# 11_FPGA_CONFIG.net
KiCad netlist of a schematic drawn in Altium Designer
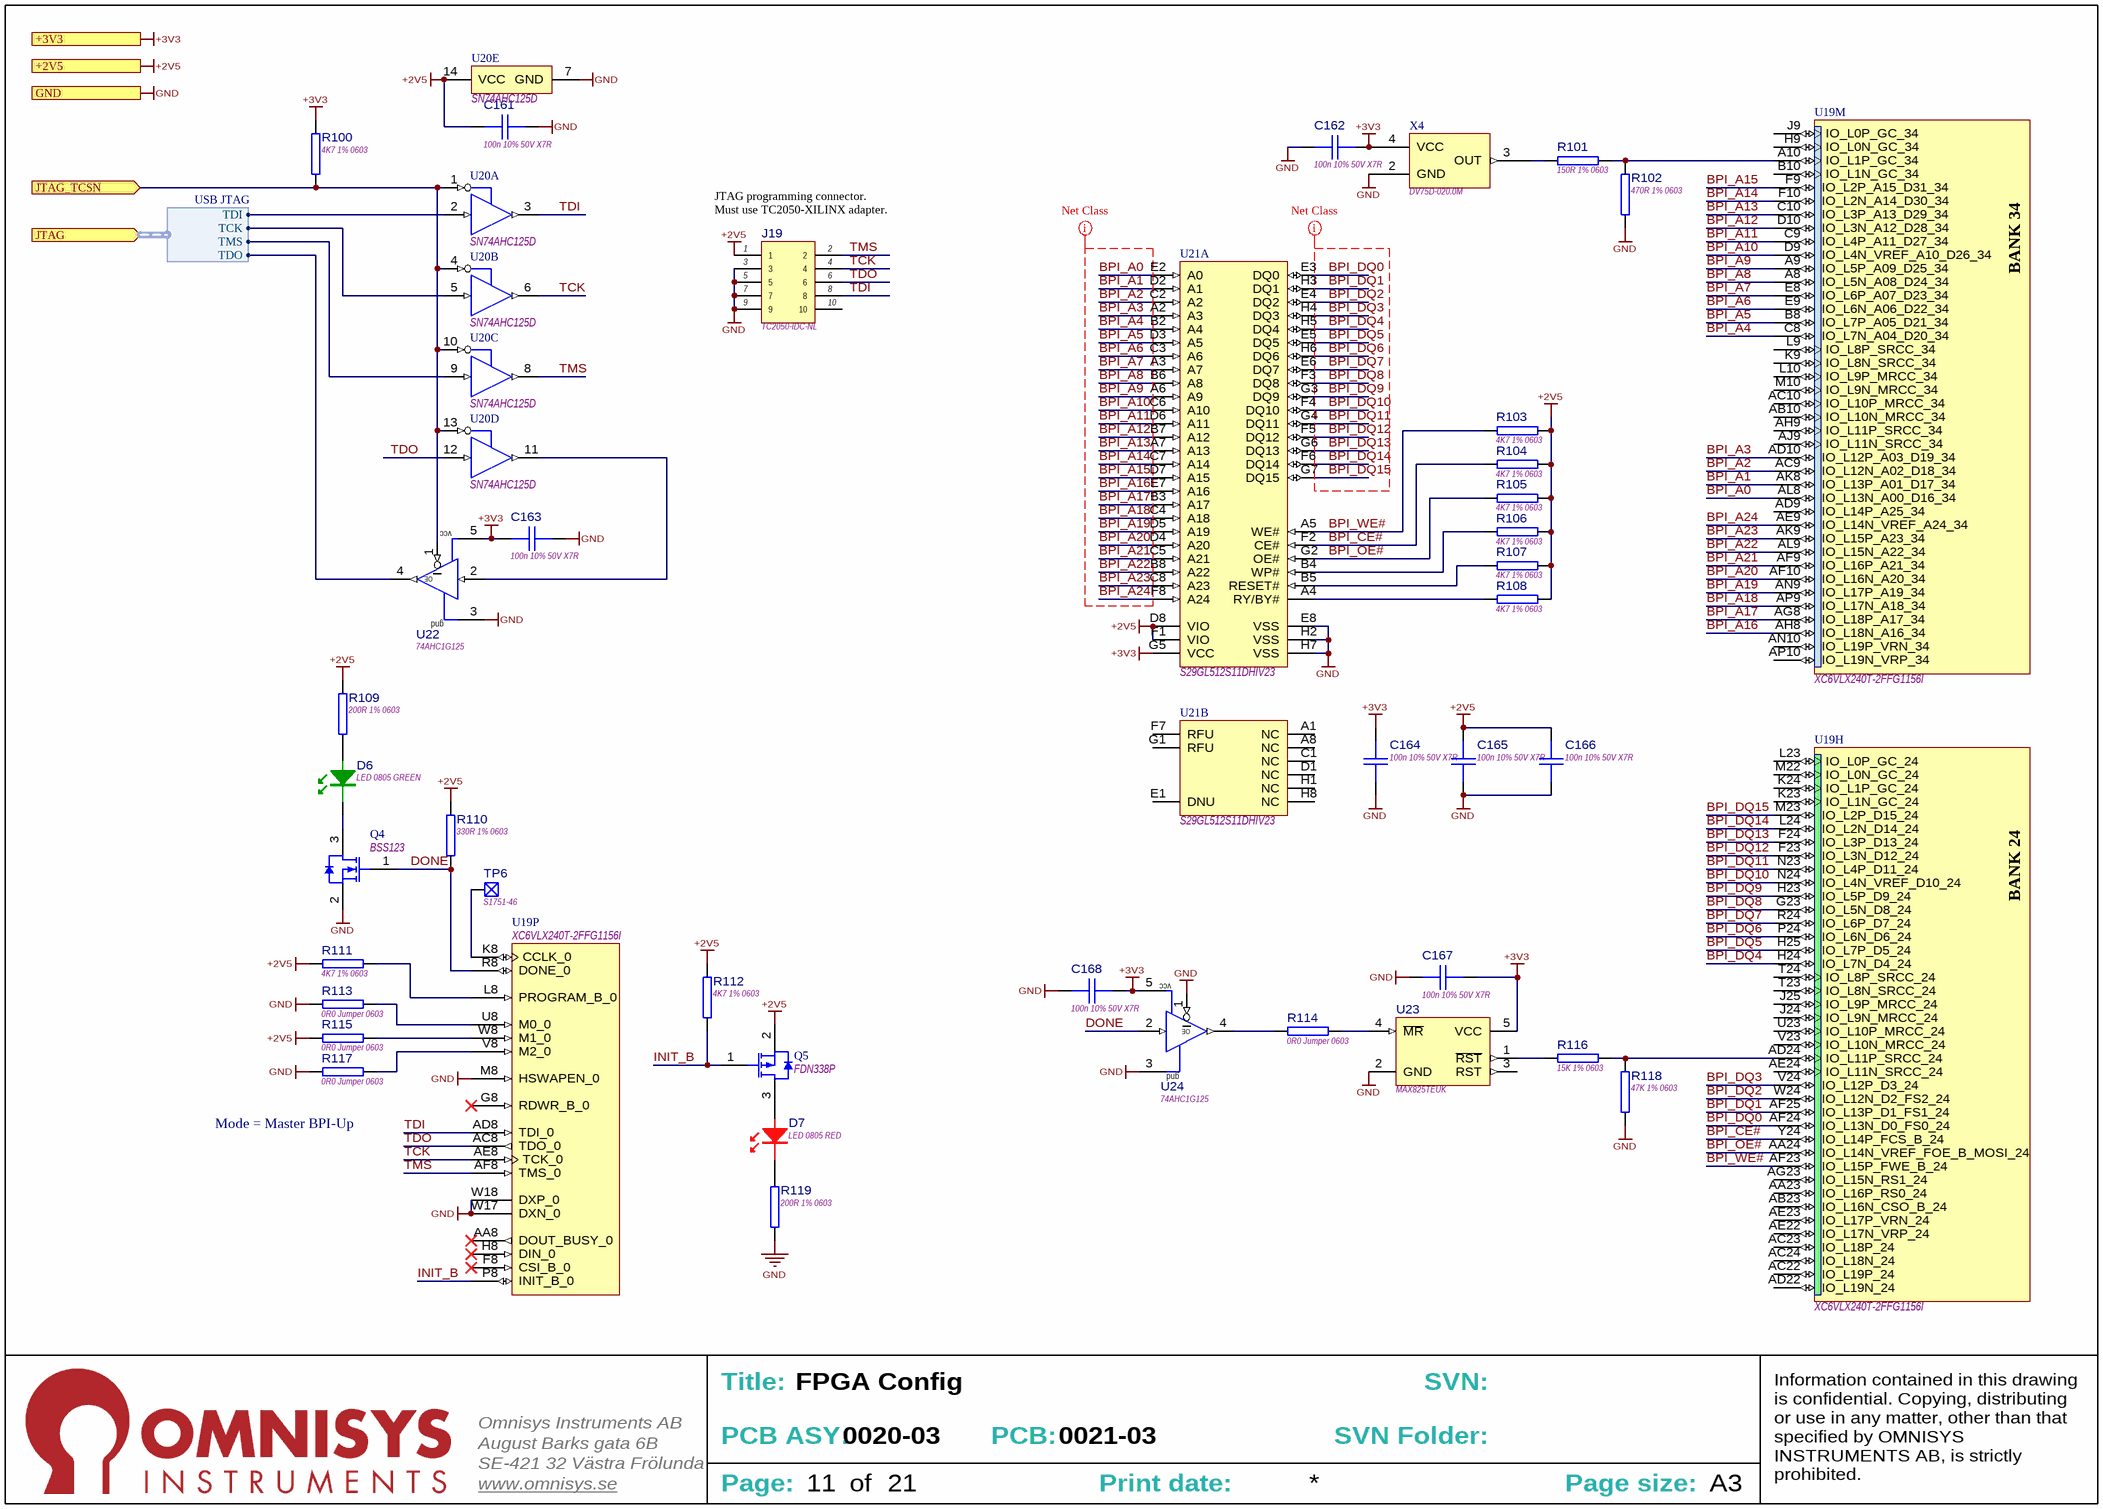
[diagram p0: [11] FPGA_CONFIG.SchDoc]

(export (version "E")
  (design (tool "Eeschema 10.0.6"))
  (components
    (comp (ref "C161")
      (value "100n 10% 50V X7R")
      (footprint "CAPC1608X90N")
      (description "Ceramic Chip Capacitor, 0603/1608")
      (fields (field (name "TOLERANCE") "10%"))
      (libsource (lib "Omnisys Vault") (part "CAP-2PIN"))
    )
    (comp (ref "C162")
      (value "100n 10% 50V X7R")
      (footprint "CAPC1608X90N")
      (description "Ceramic Chip Capacitor, 0603/1608")
      (fields (field (name "TOLERANCE") "10%"))
      (libsource (lib "Omnisys Vault") (part "CAP-2PIN"))
    )
    (comp (ref "C163")
      (value "100n 10% 50V X7R")
      (footprint "CAPC1608X90N")
      (description "Ceramic Chip Capacitor, 0603/1608")
      (fields (field (name "TOLERANCE") "10%"))
      (libsource (lib "Omnisys Vault") (part "CAP-2PIN"))
    )
    (comp (ref "C164")
      (value "100n 10% 50V X7R")
      (footprint "CAPC1608X90N")
      (description "Ceramic Chip Capacitor, 0603/1608")
      (fields (field (name "TOLERANCE") "10%"))
      (libsource (lib "Omnisys Vault") (part "CAP-2PIN"))
    )
    (comp (ref "C165")
      (value "100n 10% 50V X7R")
      (footprint "CAPC1608X90N")
      (description "Ceramic Chip Capacitor, 0603/1608")
      (fields (field (name "TOLERANCE") "10%"))
      (libsource (lib "Omnisys Vault") (part "CAP-2PIN"))
    )
    (comp (ref "C166")
      (value "100n 10% 50V X7R")
      (footprint "CAPC1608X90N")
      (description "Ceramic Chip Capacitor, 0603/1608")
      (fields (field (name "TOLERANCE") "10%"))
      (libsource (lib "Omnisys Vault") (part "CAP-2PIN"))
    )
    (comp (ref "C167")
      (value "100n 10% 50V X7R")
      (footprint "CAPC1608X90N")
      (description "Ceramic Chip Capacitor, 0603/1608")
      (fields (field (name "TOLERANCE") "10%"))
      (libsource (lib "Omnisys Vault") (part "CAP-2PIN"))
    )
    (comp (ref "C168")
      (value "100n 10% 50V X7R")
      (footprint "CAPC1608X90N")
      (description "Ceramic Chip Capacitor, 0603/1608")
      (fields (field (name "TOLERANCE") "10%"))
      (libsource (lib "Omnisys Vault") (part "CAP-2PIN"))
    )
    (comp (ref "D6")
      (value "LED 0805 GREEN")
      (footprint "LED2012-GREEN")
      (libsource (lib "Omnisys Vault") (part "LED-2PIN-GREEN"))
    )
    (comp (ref "D7")
      (value "LED 0805 RED")
      (footprint "LED2012-RED")
      (libsource (lib "Omnisys Vault") (part "LED-2PIN-RED"))
    )
    (comp (ref "J19")
      (value "TC2050-IDC-NL")
      (footprint "TC2050-IDC without connector")
      (description "CBL PLUG-OF-NAILS 10-PIN")
      (libsource (lib "Omnisys Vault") (part "CON-2ROW-10PIN"))
    )
    (comp (ref "Q4")
      (value "BSS123")
      (footprint "SOT95P230X110-3N")
      (description "MOSFET N-CH 100V 170MA SOT-23")
      (fields (field (name "VOLTAGE") "100V"))
      (libsource (lib "Omnisys Vault") (part "NEMOS-GSD-3"))
    )
    (comp (ref "Q5")
      (value "FDN338P")
      (footprint "SOT95P230X110-3N")
      (description "ON SEMICONDUCTOR - FDN338P - P CHANNEL MOSFET, -20V, 1.6A SUPER SOT-3")
      (libsource (lib "Omnisys Vault") (part "PEMOS-GSD-3"))
    )
    (comp (ref "R100")
      (value "4K7 1% 0603")
      (footprint "RESC1608N")
      (description "Thick film Chip Resistor, 0603/1608")
      (fields (field (name "POWER") "100mW") (field (name "TOLERANCE") "1%"))
      (libsource (lib "Omnisys Vault") (part "RES-2PIN"))
    )
    (comp (ref "R101")
      (value "150R 1% 0603")
      (footprint "RESC1608N")
      (description "Thick film Chip Resistor, 0603/1608")
      (fields (field (name "POWER") "100mW") (field (name "TOLERANCE") "1%"))
      (libsource (lib "Omnisys Vault") (part "RES-2PIN"))
    )
    (comp (ref "R102")
      (value "470R 1% 0603")
      (footprint "RESC1608N")
      (description "Thick film Chip Resistor, 0603/1608")
      (fields (field (name "POWER") "100mW") (field (name "TOLERANCE") "1%"))
      (libsource (lib "Omnisys Vault") (part "RES-2PIN"))
    )
    (comp (ref "R103")
      (value "4K7 1% 0603")
      (footprint "RESC1608N")
      (description "Thick film Chip Resistor, 0603/1608")
      (fields (field (name "POWER") "100mW") (field (name "TOLERANCE") "1%"))
      (libsource (lib "Omnisys Vault") (part "RES-2PIN"))
    )
    (comp (ref "R104")
      (value "4K7 1% 0603")
      (footprint "RESC1608N")
      (description "Thick film Chip Resistor, 0603/1608")
      (fields (field (name "POWER") "100mW") (field (name "TOLERANCE") "1%"))
      (libsource (lib "Omnisys Vault") (part "RES-2PIN"))
    )
    (comp (ref "R105")
      (value "4K7 1% 0603")
      (footprint "RESC1608N")
      (description "Thick film Chip Resistor, 0603/1608")
      (fields (field (name "POWER") "100mW") (field (name "TOLERANCE") "1%"))
      (libsource (lib "Omnisys Vault") (part "RES-2PIN"))
    )
    (comp (ref "R106")
      (value "4K7 1% 0603")
      (footprint "RESC1608N")
      (description "Thick film Chip Resistor, 0603/1608")
      (fields (field (name "POWER") "100mW") (field (name "TOLERANCE") "1%"))
      (libsource (lib "Omnisys Vault") (part "RES-2PIN"))
    )
    (comp (ref "R107")
      (value "4K7 1% 0603")
      (footprint "RESC1608N")
      (description "Thick film Chip Resistor, 0603/1608")
      (fields (field (name "POWER") "100mW") (field (name "TOLERANCE") "1%"))
      (libsource (lib "Omnisys Vault") (part "RES-2PIN"))
    )
    (comp (ref "R108")
      (value "4K7 1% 0603")
      (footprint "RESC1608N")
      (description "Thick film Chip Resistor, 0603/1608")
      (fields (field (name "POWER") "100mW") (field (name "TOLERANCE") "1%"))
      (libsource (lib "Omnisys Vault") (part "RES-2PIN"))
    )
    (comp (ref "R109")
      (value "200R 1% 0603")
      (footprint "RESC1608N")
      (description "Thick film Chip Resistor, 0603/1608")
      (fields (field (name "POWER") "100mW") (field (name "TOLERANCE") "1%"))
      (libsource (lib "Omnisys Vault") (part "RES-2PIN"))
    )
    (comp (ref "R110")
      (value "330R 1% 0603")
      (footprint "RESC1608N")
      (description "Thick film Chip Resistor, 0603/1608")
      (fields (field (name "POWER") "100mW") (field (name "TOLERANCE") "1%"))
      (libsource (lib "Omnisys Vault") (part "RES-2PIN"))
    )
    (comp (ref "R111")
      (value "4K7 1% 0603")
      (footprint "RESC1608N")
      (description "Thick film Chip Resistor, 0603/1608")
      (fields (field (name "POWER") "100mW") (field (name "TOLERANCE") "1%"))
      (libsource (lib "Omnisys Vault") (part "RES-2PIN"))
    )
    (comp (ref "R112")
      (value "4K7 1% 0603")
      (footprint "RESC1608N")
      (description "Thick film Chip Resistor, 0603/1608")
      (fields (field (name "POWER") "100mW") (field (name "TOLERANCE") "1%"))
      (libsource (lib "Omnisys Vault") (part "RES-2PIN"))
    )
    (comp (ref "R113")
      (value "0R0 Jumper 0603")
      (footprint "RESC1608N")
      (description "Thick film Chip Resistor, 0603/1608")
      (fields (field (name "TOLERANCE") "0%") (field (name "POWER") "0W"))
      (libsource (lib "Omnisys Vault") (part "RES-2PIN"))
    )
    (comp (ref "R114")
      (value "0R0 Jumper 0603")
      (footprint "RESC1608N")
      (description "Thick film Chip Resistor, 0603/1608")
      (fields (field (name "TOLERANCE") "0%") (field (name "POWER") "0W"))
      (libsource (lib "Omnisys Vault") (part "RES-2PIN"))
    )
    (comp (ref "R115")
      (value "0R0 Jumper 0603")
      (footprint "RESC1608N")
      (description "Thick film Chip Resistor, 0603/1608")
      (fields (field (name "TOLERANCE") "0%") (field (name "POWER") "0W"))
      (libsource (lib "Omnisys Vault") (part "RES-2PIN"))
    )
    (comp (ref "R116")
      (value "15K 1% 0603")
      (footprint "RESC1608N")
      (description "Thick film Chip Resistor, 0603/1608")
      (fields (field (name "POWER") "100mW") (field (name "TOLERANCE") "1%"))
      (libsource (lib "Omnisys Vault") (part "RES-2PIN"))
    )
    (comp (ref "R117")
      (value "0R0 Jumper 0603")
      (footprint "RESC1608N")
      (description "Thick film Chip Resistor, 0603/1608")
      (fields (field (name "TOLERANCE") "0%") (field (name "POWER") "0W"))
      (libsource (lib "Omnisys Vault") (part "RES-2PIN"))
    )
    (comp (ref "R118")
      (value "47K 1% 0603")
      (footprint "RESC1608N")
      (description "Thick film Chip Resistor, 0603/1608")
      (fields (field (name "POWER") "100mW") (field (name "TOLERANCE") "1%"))
      (libsource (lib "Omnisys Vault") (part "RES-2PIN"))
    )
    (comp (ref "R119")
      (value "200R 1% 0603")
      (footprint "RESC1608N")
      (description "Thick film Chip Resistor, 0603/1608")
      (fields (field (name "POWER") "100mW") (field (name "TOLERANCE") "1%"))
      (libsource (lib "Omnisys Vault") (part "RES-2PIN"))
    )
    (comp (ref "TP6")
      (value "S1751-46")
      (footprint "S1751-46")
      (description "SMD Test point clip")
      (libsource (lib "Omnisys Vault") (part "1-PIN_TP"))
    )
    (comp (ref "U19")
      (value "XC6VLX240T-2FFG1156I")
      (footprint "FFG1156")
      (description "FPGA Virtex-6 LXT Family 241152 Cells 40nm (CMOS) Technology 1V 1156-Pin FCBGA")
      (libsource (lib "Omnisys Vault") (part "FPGA-XVR6-XC6VXXXXXT-GA1156"))
    )
    (comp (ref "U20")
      (value "SN74AHC125D")
      (footprint "SOIC127P600X175-14N")
      (description "Buffer/Line Driver 4-CH Non-Inverting 3-ST CMOS 14-Pin SOIC Tube")
      (libsource (lib "Omnisys Vault") (part "SN74AHC125D"))
    )
    (comp (ref "U21")
      (value "S29GL512S11DHIV23")
      (footprint "BGA64C100P8X8_900X900X140")
      (description "IC FLASH MEM 512MBIT PAGE 64BGA")
      (libsource (lib "Omnisys Vault") (part "S29GL512S11DHIV23"))
    )
    (comp (ref "U22")
      (value "74AHC1G125")
      (footprint "SOT95P280X100-5N")
      (description "Single bus buffer gate with 3-state output")
      (libsource (lib "Omnisys Vault") (part "74AHC1G125"))
    )
    (comp (ref "U23")
      (value "MAX825TEUK")
      (footprint "SOT95P280X100-5N")
      (description "Microprocessor Supervisory Circuits With Watchdog Timer and Manual Reset SOT-23-5, reset th: 3.08V")
      (libsource (lib "Omnisys Vault") (part "MAX825_EUK"))
    )
    (comp (ref "U24")
      (value "74AHC1G125")
      (footprint "SOT95P280X100-5N")
      (description "Single bus buffer gate with 3-state output")
      (libsource (lib "Omnisys Vault") (part "74AHC1G125"))
    )
    (comp (ref "X4")
      (value "DV75D-020.0M")
      (footprint "DV75D")
      (description "OSC TCXO 20.000MHZ LVCMOS SMD")
      (libsource (lib "Omnisys Vault") (part "DV75D-020.0M"))
    )
  )
  (nets
    (net (code "3") (name "+2V5") (class "Default")
      (node (ref "C161") (pin "1") (pinfunction "1_1") (pintype "passive"))
      (node (ref "C165") (pin "1") (pinfunction "1_1") (pintype "passive"))
      (node (ref "C166") (pin "1") (pinfunction "1_1") (pintype "passive"))
      (node (ref "J19") (pin "1") (pinfunction "1_1") (pintype "passive"))
      (node (ref "Q5") (pin "2") (pinfunction "SOURCE_2") (pintype "passive"))
      (node (ref "R103") (pin "1") (pinfunction "1_1") (pintype "passive"))
      (node (ref "R104") (pin "1") (pinfunction "1_1") (pintype "passive"))
      (node (ref "R105") (pin "1") (pinfunction "1_1") (pintype "passive"))
      (node (ref "R106") (pin "1") (pinfunction "1_1") (pintype "passive"))
      (node (ref "R107") (pin "1") (pinfunction "1_1") (pintype "passive"))
      (node (ref "R108") (pin "1") (pinfunction "1_1") (pintype "passive"))
      (node (ref "R109") (pin "2") (pinfunction "2_2") (pintype "passive"))
      (node (ref "R110") (pin "1") (pinfunction "1_1") (pintype "passive"))
      (node (ref "R111") (pin "2") (pinfunction "2_2") (pintype "passive"))
      (node (ref "R112") (pin "1") (pinfunction "1_1") (pintype "passive"))
      (node (ref "R115") (pin "1") (pinfunction "1_1") (pintype "passive"))
      (node (ref "U20") (pin "14") (pinfunction "VCC_14") (pintype "power_in"))
      (node (ref "U21") (pin "D8") (pinfunction "VIO_D8") (pintype "power_in"))
      (node (ref "U21") (pin "F1") (pinfunction "VIO_F1") (pintype "power_in"))
    )
    (net (code "4") (name "+3V3") (class "Default")
      (node (ref "C162") (pin "1") (pinfunction "1_1") (pintype "passive"))
      (node (ref "C163") (pin "1") (pinfunction "1_1") (pintype "passive"))
      (node (ref "C164") (pin "1") (pinfunction "1_1") (pintype "passive"))
      (node (ref "C167") (pin "2") (pinfunction "2_2") (pintype "passive"))
      (node (ref "C168") (pin "1") (pinfunction "1_1") (pintype "passive"))
      (node (ref "R100") (pin "2") (pinfunction "2_2") (pintype "passive"))
      (node (ref "U21") (pin "G5") (pinfunction "VCC_G5") (pintype "power_in"))
      (node (ref "U22") (pin "5") (pinfunction "VCC_5") (pintype "power_in"))
      (node (ref "U23") (pin "5") (pinfunction "VCC_5") (pintype "power_in"))
      (node (ref "U24") (pin "5") (pinfunction "VCC_5") (pintype "power_in"))
      (node (ref "X4") (pin "4") (pinfunction "VCC_4") (pintype "power_in"))
    )
    (net (code "5") (name "/BPI_A0") (class "Default")
      (node (ref "U19") (pin "AL8") (pinfunction "IO_L13N_A00_D16_34_AL8") (pintype "bidirectional"))
      (node (ref "U21") (pin "E2") (pinfunction "A0_E2") (pintype "input"))
    )
    (net (code "6") (name "/BPI_A1") (class "Default")
      (node (ref "U19") (pin "AK8") (pinfunction "IO_L13P_A01_D17_34_AK8") (pintype "bidirectional"))
      (node (ref "U21") (pin "D2") (pinfunction "A1_D2") (pintype "input"))
    )
    (net (code "7") (name "/BPI_A2") (class "Default")
      (node (ref "U19") (pin "AC9") (pinfunction "IO_L12N_A02_D18_34_AC9") (pintype "bidirectional"))
      (node (ref "U21") (pin "C2") (pinfunction "A2_C2") (pintype "input"))
    )
    (net (code "8") (name "/BPI_A3") (class "Default")
      (node (ref "U19") (pin "AD10") (pinfunction "IO_L12P_A03_D19_34_AD10") (pintype "bidirectional"))
      (node (ref "U21") (pin "A2") (pinfunction "A3_A2") (pintype "input"))
    )
    (net (code "9") (name "/BPI_A4") (class "Default")
      (node (ref "U19") (pin "C8") (pinfunction "IO_L7N_A04_D20_34_C8") (pintype "bidirectional"))
      (node (ref "U21") (pin "B2") (pinfunction "A4_B2") (pintype "input"))
    )
    (net (code "10") (name "/BPI_A5") (class "Default")
      (node (ref "U19") (pin "B8") (pinfunction "IO_L7P_A05_D21_34_B8") (pintype "bidirectional"))
      (node (ref "U21") (pin "D3") (pinfunction "A5_D3") (pintype "input"))
    )
    (net (code "11") (name "/BPI_A6") (class "Default")
      (node (ref "U19") (pin "E9") (pinfunction "IO_L6N_A06_D22_34_E9") (pintype "bidirectional"))
      (node (ref "U21") (pin "C3") (pinfunction "A6_C3") (pintype "input"))
    )
    (net (code "12") (name "/BPI_A7") (class "Default")
      (node (ref "U19") (pin "E8") (pinfunction "IO_L6P_A07_D23_34_E8") (pintype "bidirectional"))
      (node (ref "U21") (pin "A3") (pinfunction "A7_A3") (pintype "input"))
    )
    (net (code "13") (name "/BPI_A8") (class "Default")
      (node (ref "U19") (pin "A8") (pinfunction "IO_L5N_A08_D24_34_A8") (pintype "bidirectional"))
      (node (ref "U21") (pin "B6") (pinfunction "A8_B6") (pintype "input"))
    )
    (net (code "14") (name "/BPI_A9") (class "Default")
      (node (ref "U19") (pin "A9") (pinfunction "IO_L5P_A09_D25_34_A9") (pintype "bidirectional"))
      (node (ref "U21") (pin "A6") (pinfunction "A9_A6") (pintype "input"))
    )
    (net (code "15") (name "/BPI_A10") (class "Default")
      (node (ref "U19") (pin "D9") (pinfunction "IO_L4N_VREF_A10_D26_34_D9") (pintype "bidirectional"))
      (node (ref "U21") (pin "C6") (pinfunction "A10_C6") (pintype "input"))
    )
    (net (code "16") (name "/BPI_A11") (class "Default")
      (node (ref "U19") (pin "C9") (pinfunction "IO_L4P_A11_D27_34_C9") (pintype "bidirectional"))
      (node (ref "U21") (pin "D6") (pinfunction "A11_D6") (pintype "input"))
    )
    (net (code "17") (name "/BPI_A12") (class "Default")
      (node (ref "U19") (pin "D10") (pinfunction "IO_L3N_A12_D28_34_D10") (pintype "bidirectional"))
      (node (ref "U21") (pin "B7") (pinfunction "A12_B7") (pintype "input"))
    )
    (net (code "18") (name "/BPI_A13") (class "Default")
      (node (ref "U19") (pin "C10") (pinfunction "IO_L3P_A13_D29_34_C10") (pintype "bidirectional"))
      (node (ref "U21") (pin "A7") (pinfunction "A13_A7") (pintype "input"))
    )
    (net (code "19") (name "/BPI_A14") (class "Default")
      (node (ref "U19") (pin "F10") (pinfunction "IO_L2N_A14_D30_34_F10") (pintype "bidirectional"))
      (node (ref "U21") (pin "C7") (pinfunction "A14_C7") (pintype "input"))
    )
    (net (code "20") (name "/BPI_A15") (class "Default")
      (node (ref "U19") (pin "F9") (pinfunction "IO_L2P_A15_D31_34_F9") (pintype "bidirectional"))
      (node (ref "U21") (pin "D7") (pinfunction "A15_D7") (pintype "input"))
    )
    (net (code "21") (name "/BPI_A16") (class "Default")
      (node (ref "U19") (pin "AH8") (pinfunction "IO_L18N_A16_34_AH8") (pintype "bidirectional"))
      (node (ref "U21") (pin "E7") (pinfunction "A16_E7") (pintype "input"))
    )
    (net (code "22") (name "/BPI_A17") (class "Default")
      (node (ref "U19") (pin "AG8") (pinfunction "IO_L18P_A17_34_AG8") (pintype "bidirectional"))
      (node (ref "U21") (pin "B3") (pinfunction "A17_B3") (pintype "input"))
    )
    (net (code "23") (name "/BPI_A18") (class "Default")
      (node (ref "U19") (pin "AP9") (pinfunction "IO_L17N_A18_34_AP9") (pintype "bidirectional"))
      (node (ref "U21") (pin "C4") (pinfunction "A18_C4") (pintype "input"))
    )
    (net (code "24") (name "/BPI_A19") (class "Default")
      (node (ref "U19") (pin "AN9") (pinfunction "IO_L17P_A19_34_AN9") (pintype "bidirectional"))
      (node (ref "U21") (pin "D5") (pinfunction "A19_D5") (pintype "input"))
    )
    (net (code "25") (name "/BPI_A20") (class "Default")
      (node (ref "U19") (pin "AF10") (pinfunction "IO_L16N_A20_34_AF10") (pintype "bidirectional"))
      (node (ref "U21") (pin "D4") (pinfunction "A20_D4") (pintype "input"))
    )
    (net (code "26") (name "/BPI_A21") (class "Default")
      (node (ref "U19") (pin "AF9") (pinfunction "IO_L16P_A21_34_AF9") (pintype "bidirectional"))
      (node (ref "U21") (pin "C5") (pinfunction "A21_C5") (pintype "input"))
    )
    (net (code "27") (name "/BPI_A22") (class "Default")
      (node (ref "U19") (pin "AL9") (pinfunction "IO_L15N_A22_34_AL9") (pintype "bidirectional"))
      (node (ref "U21") (pin "B8") (pinfunction "A22_B8") (pintype "input"))
    )
    (net (code "28") (name "/BPI_A23") (class "Default")
      (node (ref "U19") (pin "AK9") (pinfunction "IO_L15P_A23_34_AK9") (pintype "bidirectional"))
      (node (ref "U21") (pin "C8") (pinfunction "A23_C8") (pintype "input"))
    )
    (net (code "29") (name "/BPI_A24") (class "Default")
      (node (ref "U19") (pin "AE9") (pinfunction "IO_L14N_VREF_A24_34_AE9") (pintype "bidirectional"))
      (node (ref "U21") (pin "F8") (pinfunction "A24_F8") (pintype "input"))
    )
    (net (code "30") (name "/BPI_CE#") (class "Default")
      (node (ref "R104") (pin "2") (pinfunction "2_2") (pintype "passive"))
      (node (ref "U19") (pin "Y24") (pinfunction "IO_L14P_FCS_B_24_Y24") (pintype "bidirectional"))
      (node (ref "U21") (pin "F2") (pinfunction "CE#_F2") (pintype "input"))
    )
    (net (code "31") (name "/BPI_DQ0") (class "Default")
      (node (ref "U19") (pin "AF24") (pinfunction "IO_L13N_D0_FS0_24_AF24") (pintype "bidirectional"))
      (node (ref "U21") (pin "E3") (pinfunction "DQ0_E3") (pintype "bidirectional"))
    )
    (net (code "32") (name "/BPI_DQ1") (class "Default")
      (node (ref "U19") (pin "AF25") (pinfunction "IO_L13P_D1_FS1_24_AF25") (pintype "bidirectional"))
      (node (ref "U21") (pin "H3") (pinfunction "DQ1_H3") (pintype "bidirectional"))
    )
    (net (code "33") (name "/BPI_DQ2") (class "Default")
      (node (ref "U19") (pin "W24") (pinfunction "IO_L12N_D2_FS2_24_W24") (pintype "bidirectional"))
      (node (ref "U21") (pin "E4") (pinfunction "DQ2_E4") (pintype "bidirectional"))
    )
    (net (code "34") (name "/BPI_DQ3") (class "Default")
      (node (ref "U19") (pin "V24") (pinfunction "IO_L12P_D3_24_V24") (pintype "bidirectional"))
      (node (ref "U21") (pin "H4") (pinfunction "DQ3_H4") (pintype "bidirectional"))
    )
    (net (code "35") (name "/BPI_DQ4") (class "Default")
      (node (ref "U19") (pin "H24") (pinfunction "IO_L7N_D4_24_H24") (pintype "bidirectional"))
      (node (ref "U21") (pin "H5") (pinfunction "DQ4_H5") (pintype "bidirectional"))
    )
    (net (code "36") (name "/BPI_DQ5") (class "Default")
      (node (ref "U19") (pin "H25") (pinfunction "IO_L7P_D5_24_H25") (pintype "bidirectional"))
      (node (ref "U21") (pin "E5") (pinfunction "DQ5_E5") (pintype "bidirectional"))
    )
    (net (code "37") (name "/BPI_DQ6") (class "Default")
      (node (ref "U19") (pin "P24") (pinfunction "IO_L6N_D6_24_P24") (pintype "bidirectional"))
      (node (ref "U21") (pin "H6") (pinfunction "DQ6_H6") (pintype "bidirectional"))
    )
    (net (code "38") (name "/BPI_DQ7") (class "Default")
      (node (ref "U19") (pin "R24") (pinfunction "IO_L6P_D7_24_R24") (pintype "bidirectional"))
      (node (ref "U21") (pin "E6") (pinfunction "DQ7_E6") (pintype "bidirectional"))
    )
    (net (code "39") (name "/BPI_DQ8") (class "Default")
      (node (ref "U19") (pin "G23") (pinfunction "IO_L5N_D8_24_G23") (pintype "bidirectional"))
      (node (ref "U21") (pin "F3") (pinfunction "DQ8_F3") (pintype "bidirectional"))
    )
    (net (code "40") (name "/BPI_DQ9") (class "Default")
      (node (ref "U19") (pin "H23") (pinfunction "IO_L5P_D9_24_H23") (pintype "bidirectional"))
      (node (ref "U21") (pin "G3") (pinfunction "DQ9_G3") (pintype "bidirectional"))
    )
    (net (code "41") (name "/BPI_DQ10") (class "Default")
      (node (ref "U19") (pin "N24") (pinfunction "IO_L4N_VREF_D10_24_N24") (pintype "bidirectional"))
      (node (ref "U21") (pin "F4") (pinfunction "DQ10_F4") (pintype "bidirectional"))
    )
    (net (code "42") (name "/BPI_DQ11") (class "Default")
      (node (ref "U19") (pin "N23") (pinfunction "IO_L4P_D11_24_N23") (pintype "bidirectional"))
      (node (ref "U21") (pin "G4") (pinfunction "DQ11_G4") (pintype "bidirectional"))
    )
    (net (code "43") (name "/BPI_DQ12") (class "Default")
      (node (ref "U19") (pin "F23") (pinfunction "IO_L3N_D12_24_F23") (pintype "bidirectional"))
      (node (ref "U21") (pin "F5") (pinfunction "DQ12_F5") (pintype "bidirectional"))
    )
    (net (code "44") (name "/BPI_DQ13") (class "Default")
      (node (ref "U19") (pin "F24") (pinfunction "IO_L3P_D13_24_F24") (pintype "bidirectional"))
      (node (ref "U21") (pin "G6") (pinfunction "DQ13_G6") (pintype "bidirectional"))
    )
    (net (code "45") (name "/BPI_DQ14") (class "Default")
      (node (ref "U19") (pin "L24") (pinfunction "IO_L2N_D14_24_L24") (pintype "bidirectional"))
      (node (ref "U21") (pin "F6") (pinfunction "DQ14_F6") (pintype "bidirectional"))
    )
    (net (code "46") (name "/BPI_DQ15") (class "Default")
      (node (ref "U19") (pin "M23") (pinfunction "IO_L2P_D15_24_M23") (pintype "bidirectional"))
      (node (ref "U21") (pin "G7") (pinfunction "DQ15_G7") (pintype "bidirectional"))
    )
    (net (code "47") (name "/BPI_OE#") (class "Default")
      (node (ref "R105") (pin "2") (pinfunction "2_2") (pintype "passive"))
      (node (ref "U19") (pin "AA24") (pinfunction "IO_L14N_VREF_FOE_B_MOSI_24_AA24") (pintype "bidirectional"))
      (node (ref "U21") (pin "G2") (pinfunction "OE#_G2") (pintype "input"))
    )
    (net (code "48") (name "/BPI_WE#") (class "Default")
      (node (ref "R103") (pin "2") (pinfunction "2_2") (pintype "passive"))
      (node (ref "U19") (pin "AF23") (pinfunction "IO_L15P_FWE_B_24_AF23") (pintype "bidirectional"))
      (node (ref "U21") (pin "A5") (pinfunction "WE#_A5") (pintype "input"))
    )
    (net (code "49") (name "/DONE") (class "Default")
      (node (ref "Q4") (pin "1") (pinfunction "G_1") (pintype "passive"))
      (node (ref "R110") (pin "2") (pinfunction "2_2") (pintype "passive"))
      (node (ref "U19") (pin "R8") (pinfunction "DONE_0_R8") (pintype "bidirectional"))
      (node (ref "U24") (pin "2") (pinfunction "B_2") (pintype "input"))
    )
    (net (code "50") (name "/INIT_B") (class "Default")
      (node (ref "Q5") (pin "1") (pinfunction "GATE_1") (pintype "passive"))
      (node (ref "R112") (pin "2") (pinfunction "2_2") (pintype "passive"))
      (node (ref "U19") (pin "P8") (pinfunction "INIT_B_0_P8") (pintype "bidirectional"))
    )
    (net (code "51") (name "/JTAG_TCSN") (class "Default")
      (node (ref "R100") (pin "1") (pinfunction "1_1") (pintype "passive"))
      (node (ref "U20") (pin "1") (pinfunction "1OE#_1") (pintype "input"))
      (node (ref "U20") (pin "10") (pinfunction "3OE#_10") (pintype "input"))
      (node (ref "U20") (pin "13") (pinfunction "4OE#_13") (pintype "input"))
      (node (ref "U20") (pin "4") (pinfunction "2OE#_4") (pintype "input"))
      (node (ref "U22") (pin "1") (pinfunction "~{O}E_1") (pintype "input"))
    )
    (net (code "52") (name "/TCK") (class "Default")
      (node (ref "J19") (pin "4") (pinfunction "4_4") (pintype "passive"))
      (node (ref "U19") (pin "AE8") (pinfunction "TCK_0_AE8") (pintype "input"))
      (node (ref "U20") (pin "6") (pinfunction "2Y_6") (pintype "output"))
    )
    (net (code "53") (name "/TDI") (class "Default")
      (node (ref "J19") (pin "8") (pinfunction "8_8") (pintype "passive"))
      (node (ref "U19") (pin "AD8") (pinfunction "TDI_0_AD8") (pintype "input"))
      (node (ref "U20") (pin "3") (pinfunction "1Y_3") (pintype "output"))
    )
    (net (code "54") (name "/TDO") (class "Default")
      (node (ref "J19") (pin "6") (pinfunction "6_6") (pintype "passive"))
      (node (ref "U19") (pin "AC8") (pinfunction "TDO_0_AC8") (pintype "output"))
      (node (ref "U20") (pin "12") (pinfunction "4A_12") (pintype "input"))
    )
    (net (code "55") (name "/TMS") (class "Default")
      (node (ref "J19") (pin "2") (pinfunction "2_2") (pintype "passive"))
      (node (ref "U19") (pin "AF8") (pinfunction "TMS_0_AF8") (pintype "input"))
      (node (ref "U20") (pin "8") (pinfunction "3Y_8") (pintype "output"))
    )
    (net (code "57") (name "GND") (class "Default")
      (node (ref "C161") (pin "2") (pinfunction "2_2") (pintype "passive"))
      (node (ref "C162") (pin "2") (pinfunction "2_2") (pintype "passive"))
      (node (ref "C163") (pin "2") (pinfunction "2_2") (pintype "passive"))
      (node (ref "C164") (pin "2") (pinfunction "2_2") (pintype "passive"))
      (node (ref "C165") (pin "2") (pinfunction "2_2") (pintype "passive"))
      (node (ref "C166") (pin "2") (pinfunction "2_2") (pintype "passive"))
      (node (ref "C167") (pin "1") (pinfunction "1_1") (pintype "passive"))
      (node (ref "C168") (pin "2") (pinfunction "2_2") (pintype "passive"))
      (node (ref "J19") (pin "3") (pinfunction "3_3") (pintype "passive"))
      (node (ref "J19") (pin "5") (pinfunction "5_5") (pintype "passive"))
      (node (ref "J19") (pin "7") (pinfunction "7_7") (pintype "passive"))
      (node (ref "J19") (pin "9") (pinfunction "9_9") (pintype "passive"))
      (node (ref "Q4") (pin "2") (pinfunction "S_2") (pintype "passive"))
      (node (ref "R102") (pin "1") (pinfunction "1_1") (pintype "passive"))
      (node (ref "R113") (pin "1") (pinfunction "1_1") (pintype "passive"))
      (node (ref "R117") (pin "1") (pinfunction "1_1") (pintype "passive"))
      (node (ref "R118") (pin "1") (pinfunction "1_1") (pintype "passive"))
      (node (ref "R119") (pin "1") (pinfunction "1_1") (pintype "passive"))
      (node (ref "U19") (pin "M8") (pinfunction "HSWAPEN_0_M8") (pintype "input"))
      (node (ref "U19") (pin "W17") (pinfunction "DXN_0_W17") (pintype "passive"))
      (node (ref "U19") (pin "W18") (pinfunction "DXP_0_W18") (pintype "passive"))
      (node (ref "U20") (pin "7") (pinfunction "GND_7") (pintype "power_in"))
      (node (ref "U21") (pin "E8") (pinfunction "VSS_E8") (pintype "power_in"))
      (node (ref "U21") (pin "H2") (pinfunction "VSS_H2") (pintype "power_in"))
      (node (ref "U21") (pin "H7") (pinfunction "VSS_H7") (pintype "power_in"))
      (node (ref "U22") (pin "3") (pinfunction "GND_3") (pintype "power_in"))
      (node (ref "U23") (pin "2") (pinfunction "GND_2") (pintype "power_in"))
      (node (ref "U24") (pin "1") (pinfunction "~{O}E_1") (pintype "input"))
      (node (ref "U24") (pin "3") (pinfunction "GND_3") (pintype "power_in"))
      (node (ref "X4") (pin "2") (pinfunction "GND_2") (pintype "power_in"))
    )
    (net (code "58") (name "Net-(D6-Pad2)") (class "Default")
      (node (ref "D6") (pin "2") (pintype "passive"))
      (node (ref "R109") (pin "1") (pinfunction "1_1") (pintype "passive"))
    )
    (net (code "59") (name "Net-(D7-Pad1)") (class "Default")
      (node (ref "D7") (pin "1") (pintype "passive"))
      (node (ref "R119") (pin "2") (pinfunction "2_2") (pintype "passive"))
    )
    (net (code "60") (name "Net-(Q4-D)") (class "Default")
      (node (ref "D6") (pin "1") (pintype "passive"))
      (node (ref "Q4") (pin "3") (pinfunction "D_3") (pintype "passive"))
    )
    (net (code "61") (name "Net-(Q5-DRAIN)") (class "Default")
      (node (ref "D7") (pin "2") (pintype "passive"))
      (node (ref "Q5") (pin "3") (pinfunction "DRAIN_3") (pintype "passive"))
    )
    (net (code "62") (name "Net-(U19H-IO_L11P_SRCC_24)") (class "Default")
      (node (ref "R116") (pin "2") (pinfunction "2_2") (pintype "passive"))
      (node (ref "R118") (pin "2") (pinfunction "2_2") (pintype "passive"))
      (node (ref "U19") (pin "AD24") (pinfunction "IO_L11P_SRCC_24_AD24") (pintype "bidirectional"))
    )
    (net (code "63") (name "Net-(U19M-IO_L1P_GC_34)") (class "Default")
      (node (ref "R101") (pin "2") (pinfunction "2_2") (pintype "passive"))
      (node (ref "R102") (pin "2") (pinfunction "2_2") (pintype "passive"))
      (node (ref "U19") (pin "A10") (pinfunction "IO_L1P_GC_34_A10") (pintype "bidirectional"))
    )
    (net (code "64") (name "Net-(U19P-CCLK_0)") (class "Default")
      (node (ref "TP6") (pin "1") (pinfunction "1_1") (pintype "passive"))
      (node (ref "U19") (pin "K8") (pinfunction "CCLK_0_K8") (pintype "bidirectional"))
    )
    (net (code "65") (name "Net-(U19P-M0_0)") (class "Default")
      (node (ref "R113") (pin "2") (pinfunction "2_2") (pintype "passive"))
      (node (ref "U19") (pin "U8") (pinfunction "M0_0_U8") (pintype "input"))
    )
    (net (code "66") (name "Net-(U19P-M1_0)") (class "Default")
      (node (ref "R115") (pin "2") (pinfunction "2_2") (pintype "passive"))
      (node (ref "U19") (pin "W8") (pinfunction "M1_0_W8") (pintype "input"))
    )
    (net (code "67") (name "Net-(U19P-M2_0)") (class "Default")
      (node (ref "R117") (pin "2") (pinfunction "2_2") (pintype "passive"))
      (node (ref "U19") (pin "V8") (pinfunction "M2_0_V8") (pintype "input"))
    )
    (net (code "68") (name "Net-(U19P-PROGRAM_B_0)") (class "Default")
      (node (ref "R111") (pin "1") (pinfunction "1_1") (pintype "passive"))
      (node (ref "U19") (pin "L8") (pinfunction "PROGRAM_B_0_L8") (pintype "input"))
    )
    (net (code "69") (name "Net-(U20D-4Y)") (class "Default")
      (node (ref "U20") (pin "11") (pinfunction "4Y_11") (pintype "output"))
      (node (ref "U22") (pin "2") (pinfunction "B_2") (pintype "input"))
    )
    (net (code "70") (name "Net-(U21A-RESET#)") (class "Default")
      (node (ref "R107") (pin "2") (pinfunction "2_2") (pintype "passive"))
      (node (ref "U21") (pin "B5") (pinfunction "RESET#_B5") (pintype "input"))
    )
    (net (code "71") (name "Net-(U21A-RY{slash}BY#)") (class "Default")
      (node (ref "R108") (pin "2") (pinfunction "2_2") (pintype "passive"))
      (node (ref "U21") (pin "A4") (pinfunction "RY/BY#_A4") (pintype "tri_state"))
    )
    (net (code "72") (name "Net-(U21A-WP#)") (class "Default")
      (node (ref "R106") (pin "2") (pinfunction "2_2") (pintype "passive"))
      (node (ref "U21") (pin "B4") (pinfunction "WP#_B4") (pintype "input"))
    )
    (net (code "73") (name "Net-(U23-~{MR})") (class "Default")
      (node (ref "R114") (pin "1") (pinfunction "1_1") (pintype "passive"))
      (node (ref "U23") (pin "4") (pinfunction "~{MR}_4") (pintype "input"))
    )
    (net (code "74") (name "Net-(U23-~{RST})") (class "Default")
      (node (ref "R116") (pin "1") (pinfunction "1_1") (pintype "passive"))
      (node (ref "U23") (pin "1") (pinfunction "~{RST}_1") (pintype "output"))
    )
    (net (code "75") (name "Net-(U24-Y)") (class "Default")
      (node (ref "R114") (pin "2") (pinfunction "2_2") (pintype "passive"))
      (node (ref "U24") (pin "4") (pinfunction "Y_4") (pintype "output"))
    )
    (net (code "76") (name "Net-(X4-OUT)") (class "Default")
      (node (ref "R101") (pin "1") (pinfunction "1_1") (pintype "passive"))
      (node (ref "X4") (pin "3") (pinfunction "OUT_3") (pintype "output"))
    )
    (net (code "77") (name "unconnected-(J19-Pad10)") (class "Default")
      (node (ref "J19") (pin "10") (pinfunction "10_10") (pintype "passive"))
    )
    (net (code "78") (name "unconnected-(U19H-IO_L0N_GC_24-PadM22)") (class "Default")
      (node (ref "U19") (pin "M22") (pinfunction "IO_L0N_GC_24_M22") (pintype "bidirectional"))
    )
    (net (code "79") (name "unconnected-(U19H-IO_L0P_GC_24-PadL23)") (class "Default")
      (node (ref "U19") (pin "L23") (pinfunction "IO_L0P_GC_24_L23") (pintype "bidirectional"))
    )
    (net (code "80") (name "unconnected-(U19H-IO_L1N_GC_24-PadK23)") (class "Default")
      (node (ref "U19") (pin "K23") (pinfunction "IO_L1N_GC_24_K23") (pintype "bidirectional"))
    )
    (net (code "81") (name "unconnected-(U19H-IO_L1P_GC_24-PadK24)") (class "Default")
      (node (ref "U19") (pin "K24") (pinfunction "IO_L1P_GC_24_K24") (pintype "bidirectional"))
    )
    (net (code "82") (name "unconnected-(U19H-IO_L8N_SRCC_24-PadT23)") (class "Default")
      (node (ref "U19") (pin "T23") (pinfunction "IO_L8N_SRCC_24_T23") (pintype "bidirectional"))
    )
    (net (code "83") (name "unconnected-(U19H-IO_L8P_SRCC_24-PadT24)") (class "Default")
      (node (ref "U19") (pin "T24") (pinfunction "IO_L8P_SRCC_24_T24") (pintype "bidirectional"))
    )
    (net (code "84") (name "unconnected-(U19H-IO_L9N_MRCC_24-PadJ24)") (class "Default")
      (node (ref "U19") (pin "J24") (pinfunction "IO_L9N_MRCC_24_J24") (pintype "bidirectional"))
    )
    (net (code "85") (name "unconnected-(U19H-IO_L9P_MRCC_24-PadJ25)") (class "Default")
      (node (ref "U19") (pin "J25") (pinfunction "IO_L9P_MRCC_24_J25") (pintype "bidirectional"))
    )
    (net (code "86") (name "unconnected-(U19H-IO_L10N_MRCC_24-PadV23)") (class "Default")
      (node (ref "U19") (pin "V23") (pinfunction "IO_L10N_MRCC_24_V23") (pintype "bidirectional"))
    )
    (net (code "87") (name "unconnected-(U19H-IO_L10P_MRCC_24-PadU23)") (class "Default")
      (node (ref "U19") (pin "U23") (pinfunction "IO_L10P_MRCC_24_U23") (pintype "bidirectional"))
    )
    (net (code "88") (name "unconnected-(U19H-IO_L11N_SRCC_24-PadAE24)") (class "Default")
      (node (ref "U19") (pin "AE24") (pinfunction "IO_L11N_SRCC_24_AE24") (pintype "bidirectional"))
    )
    (net (code "89") (name "unconnected-(U19H-IO_L15N_RS1_24-PadAG23)") (class "Default")
      (node (ref "U19") (pin "AG23") (pinfunction "IO_L15N_RS1_24_AG23") (pintype "bidirectional"))
    )
    (net (code "90") (name "unconnected-(U19H-IO_L16N_CSO_B_24-PadAB23)") (class "Default")
      (node (ref "U19") (pin "AB23") (pinfunction "IO_L16N_CSO_B_24_AB23") (pintype "bidirectional"))
    )
    (net (code "91") (name "unconnected-(U19H-IO_L16P_RS0_24-PadAA23)") (class "Default")
      (node (ref "U19") (pin "AA23") (pinfunction "IO_L16P_RS0_24_AA23") (pintype "bidirectional"))
    )
    (net (code "92") (name "unconnected-(U19H-IO_L17N_VRP_24-PadAE22)") (class "Default")
      (node (ref "U19") (pin "AE22") (pinfunction "IO_L17N_VRP_24_AE22") (pintype "bidirectional"))
    )
    (net (code "93") (name "unconnected-(U19H-IO_L17P_VRN_24-PadAE23)") (class "Default")
      (node (ref "U19") (pin "AE23") (pinfunction "IO_L17P_VRN_24_AE23") (pintype "bidirectional"))
    )
    (net (code "94") (name "unconnected-(U19H-IO_L18N_24-PadAC24)") (class "Default")
      (node (ref "U19") (pin "AC24") (pinfunction "IO_L18N_24_AC24") (pintype "bidirectional"))
    )
    (net (code "95") (name "unconnected-(U19H-IO_L18P_24-PadAC23)") (class "Default")
      (node (ref "U19") (pin "AC23") (pinfunction "IO_L18P_24_AC23") (pintype "bidirectional"))
    )
    (net (code "96") (name "unconnected-(U19H-IO_L19N_24-PadAD22)") (class "Default")
      (node (ref "U19") (pin "AD22") (pinfunction "IO_L19N_24_AD22") (pintype "bidirectional"))
    )
    (net (code "97") (name "unconnected-(U19H-IO_L19P_24-PadAC22)") (class "Default")
      (node (ref "U19") (pin "AC22") (pinfunction "IO_L19P_24_AC22") (pintype "bidirectional"))
    )
    (net (code "98") (name "unconnected-(U19M-IO_L0N_GC_34-PadH9)") (class "Default")
      (node (ref "U19") (pin "H9") (pinfunction "IO_L0N_GC_34_H9") (pintype "bidirectional"))
    )
    (net (code "99") (name "unconnected-(U19M-IO_L0P_GC_34-PadJ9)") (class "Default")
      (node (ref "U19") (pin "J9") (pinfunction "IO_L0P_GC_34_J9") (pintype "bidirectional"))
    )
    (net (code "100") (name "unconnected-(U19M-IO_L1N_GC_34-PadB10)") (class "Default")
      (node (ref "U19") (pin "B10") (pinfunction "IO_L1N_GC_34_B10") (pintype "bidirectional"))
    )
    (net (code "101") (name "unconnected-(U19M-IO_L8N_SRCC_34-PadK9)") (class "Default")
      (node (ref "U19") (pin "K9") (pinfunction "IO_L8N_SRCC_34_K9") (pintype "bidirectional"))
    )
    (net (code "102") (name "unconnected-(U19M-IO_L8P_SRCC_34-PadL9)") (class "Default")
      (node (ref "U19") (pin "L9") (pinfunction "IO_L8P_SRCC_34_L9") (pintype "bidirectional"))
    )
    (net (code "103") (name "unconnected-(U19M-IO_L9N_MRCC_34-PadM10)") (class "Default")
      (node (ref "U19") (pin "M10") (pinfunction "IO_L9N_MRCC_34_M10") (pintype "bidirectional"))
    )
    (net (code "104") (name "unconnected-(U19M-IO_L9P_MRCC_34-PadL10)") (class "Default")
      (node (ref "U19") (pin "L10") (pinfunction "IO_L9P_MRCC_34_L10") (pintype "bidirectional"))
    )
    (net (code "105") (name "unconnected-(U19M-IO_L10N_MRCC_34-PadAB10)") (class "Default")
      (node (ref "U19") (pin "AB10") (pinfunction "IO_L10N_MRCC_34_AB10") (pintype "bidirectional"))
    )
    (net (code "106") (name "unconnected-(U19M-IO_L10P_MRCC_34-PadAC10)") (class "Default")
      (node (ref "U19") (pin "AC10") (pinfunction "IO_L10P_MRCC_34_AC10") (pintype "bidirectional"))
    )
    (net (code "107") (name "unconnected-(U19M-IO_L11N_SRCC_34-PadAJ9)") (class "Default")
      (node (ref "U19") (pin "AJ9") (pinfunction "IO_L11N_SRCC_34_AJ9") (pintype "bidirectional"))
    )
    (net (code "108") (name "unconnected-(U19M-IO_L11P_SRCC_34-PadAH9)") (class "Default")
      (node (ref "U19") (pin "AH9") (pinfunction "IO_L11P_SRCC_34_AH9") (pintype "bidirectional"))
    )
    (net (code "109") (name "unconnected-(U19M-IO_L14P_A25_34-PadAD9)") (class "Default")
      (node (ref "U19") (pin "AD9") (pinfunction "IO_L14P_A25_34_AD9") (pintype "bidirectional"))
    )
    (net (code "110") (name "unconnected-(U19M-IO_L19N_VRP_34-PadAP10)") (class "Default")
      (node (ref "U19") (pin "AP10") (pinfunction "IO_L19N_VRP_34_AP10") (pintype "bidirectional"))
    )
    (net (code "111") (name "unconnected-(U19M-IO_L19P_VRN_34-PadAN10)") (class "Default")
      (node (ref "U19") (pin "AN10") (pinfunction "IO_L19P_VRN_34_AN10") (pintype "bidirectional"))
    )
    (net (code "112") (name "unconnected-(U19P-CSI_B_0-PadF8)") (class "Default")
      (node (ref "U19") (pin "F8") (pinfunction "CSI_B_0_F8") (pintype "input+no_connect"))
    )
    (net (code "113") (name "unconnected-(U19P-DIN_0-PadH8)") (class "Default")
      (node (ref "U19") (pin "H8") (pinfunction "DIN_0_H8") (pintype "input+no_connect"))
    )
    (net (code "114") (name "unconnected-(U19P-DOUT_BUSY_0-PadAA8)") (class "Default")
      (node (ref "U19") (pin "AA8") (pinfunction "DOUT_BUSY_0_AA8") (pintype "output+no_connect"))
    )
    (net (code "115") (name "unconnected-(U19P-RDWR_B_0-PadG8)") (class "Default")
      (node (ref "U19") (pin "G8") (pinfunction "RDWR_B_0_G8") (pintype "input+no_connect"))
    )
    (net (code "116") (name "unconnected-(U20A-1A-Pad2)") (class "Default")
      (node (ref "U20") (pin "2") (pinfunction "1A_2") (pintype "input"))
    )
    (net (code "117") (name "unconnected-(U20B-2A-Pad5)") (class "Default")
      (node (ref "U20") (pin "5") (pinfunction "2A_5") (pintype "input"))
    )
    (net (code "118") (name "unconnected-(U20C-3A-Pad9)") (class "Default")
      (node (ref "U20") (pin "9") (pinfunction "3A_9") (pintype "input"))
    )
    (net (code "119") (name "unconnected-(U21B-DNU-PadE1)") (class "Default")
      (node (ref "U21") (pin "E1") (pinfunction "DNU_E1") (pintype "passive"))
    )
    (net (code "120") (name "unconnected-(U21B-NC-PadA1)") (class "Default")
      (node (ref "U21") (pin "A1") (pinfunction "NC_A1") (pintype "passive"))
    )
    (net (code "121") (name "unconnected-(U21B-NC-PadA8)") (class "Default")
      (node (ref "U21") (pin "A8") (pinfunction "NC_A8") (pintype "passive"))
    )
    (net (code "122") (name "unconnected-(U21B-NC-PadC1)") (class "Default")
      (node (ref "U21") (pin "C1") (pinfunction "NC_C1") (pintype "passive"))
    )
    (net (code "123") (name "unconnected-(U21B-NC-PadD1)") (class "Default")
      (node (ref "U21") (pin "D1") (pinfunction "NC_D1") (pintype "passive"))
    )
    (net (code "124") (name "unconnected-(U21B-NC-PadH1)") (class "Default")
      (node (ref "U21") (pin "H1") (pinfunction "NC_H1") (pintype "passive"))
    )
    (net (code "125") (name "unconnected-(U21B-NC-PadH8)") (class "Default")
      (node (ref "U21") (pin "H8") (pinfunction "NC_H8") (pintype "passive"))
    )
    (net (code "126") (name "unconnected-(U21B-RFU-PadF7)") (class "Default")
      (node (ref "U21") (pin "F7") (pinfunction "RFU_F7") (pintype "passive"))
    )
    (net (code "127") (name "unconnected-(U21B-RFU-PadG1)") (class "Default")
      (node (ref "U21") (pin "G1") (pinfunction "RFU_G1") (pintype "passive"))
    )
    (net (code "128") (name "unconnected-(U22-Y-Pad4)") (class "Default")
      (node (ref "U22") (pin "4") (pinfunction "Y_4") (pintype "output"))
    )
    (net (code "129") (name "unconnected-(U23-RST-Pad3)") (class "Default")
      (node (ref "U23") (pin "3") (pinfunction "RST_3") (pintype "output"))
    )
  )
)
